# MCU.net
KiCad netlist of a schematic drawn in Altium Designer
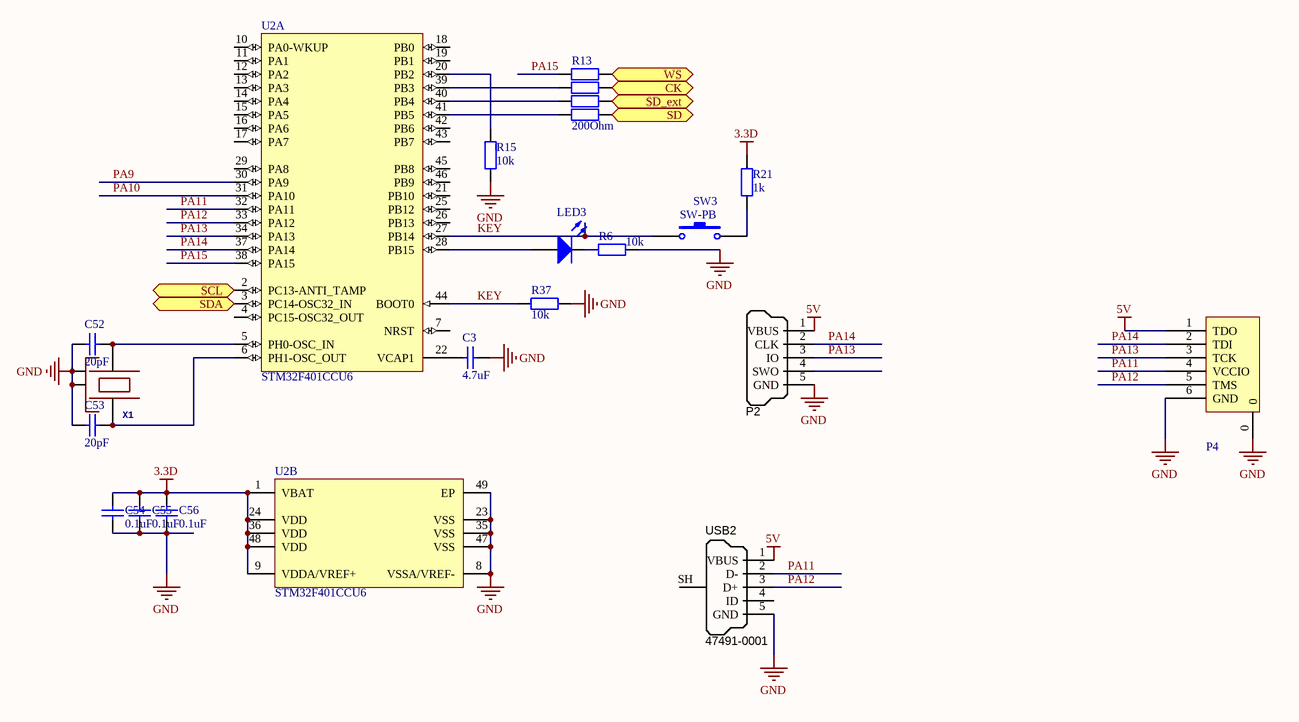
[diagram p0: MCU.SchDoc]

(export (version "E")
  (design (tool "Eeschema 10.0.6"))
  (components
    (comp (ref "C3")
      (value "4.7uF")
      (footprint "0603L")
      (description "Capacitor")
      (fields (field (name "Comment") "Cap") (field (name "PUBLISHER") "Altium Limited"))
      (libsource (lib "RTC6705") (part "Cap"))
    )
    (comp (ref "C52")
      (value "20pF")
      (footprint "0402")
      (description "Capacitor")
      (fields (field (name "Comment") "Cap") (field (name "PUBLISHER") "Altium Limited"))
      (libsource (lib "RTC6705") (part "Cap"))
    )
    (comp (ref "C53")
      (value "20pF")
      (footprint "0402")
      (description "Capacitor")
      (fields (field (name "Comment") "Cap") (field (name "PUBLISHER") "Altium Limited"))
      (libsource (lib "RTC6705") (part "Cap"))
    )
    (comp (ref "C54")
      (value "0.1uF")
      (footprint "0402")
      (description "Capacitor")
      (fields (field (name "Comment") "Cap") (field (name "PUBLISHER") "Altium Limited"))
      (libsource (lib "RTC6705") (part "Cap"))
    )
    (comp (ref "C55")
      (value "0.1uF")
      (footprint "0402")
      (description "Capacitor")
      (fields (field (name "Comment") "Cap") (field (name "PUBLISHER") "Altium Limited"))
      (libsource (lib "RTC6705") (part "Cap"))
    )
    (comp (ref "C56")
      (value "0.1uF")
      (footprint "0402")
      (description "Capacitor")
      (fields (field (name "Comment") "Cap") (field (name "PUBLISHER") "Altium Limited"))
      (libsource (lib "RTC6705") (part "Cap"))
    )
    (comp (ref "LED3")
      (value "LED0")
      (footprint "0603")
      (description "Typical INFRARED GaAs LED")
      (fields (field (name "PUBLISHER") "Altium Limited"))
      (libsource (lib "Miscellaneous Devices") (part "LED0"))
    )
    (comp (ref "P2")
      (value "SWD_MicroUSB")
      (footprint "MICRO-YZX")
      (description "Connector SMD USB Micro Type B middle mount")
      (libsource (lib "sch") (part "SWD_MicroUSB"))
    )
    (comp (ref "P4") (value "JTAG-6P") (footprint "GH1.25-6") (libsource (lib "sch") (part "JTAG-6P")))
    (comp (ref "R6")
      (value "10k")
      (footprint "0402")
      (description "Resistor")
      (fields (field (name "PUBLISHER") "Altium Limited"))
      (libsource (lib "Miscellaneous Devices") (part "Res2"))
    )
    (comp (ref "R13")
      (value "200Ohm")
      (footprint "0402X4")
      (description "Resistor")
      (fields (field (name "Comment") "Res*4") (field (name "PUBLISHER") "Altium Limited"))
      (libsource (lib "sch") (part "Res*4"))
    )
    (comp (ref "R15")
      (value "10k")
      (footprint "0402")
      (description "Resistor")
      (fields (field (name "PUBLISHER") "Altium Limited"))
      (libsource (lib "") (part "Res2_1"))
    )
    (comp (ref "R21")
      (value "1k")
      (footprint "0402")
      (description "Resistor")
      (fields (field (name "PUBLISHER") "Altium Limited"))
      (libsource (lib "") (part "Res2_2"))
    )
    (comp (ref "R37")
      (value "10k")
      (footprint "0402")
      (description "Resistor")
      (fields (field (name "Comment") "Res2") (field (name "PUBLISHER") "Altium Limited"))
      (libsource (lib "RTC6705") (part "Res2"))
    )
    (comp (ref "SW3")
      (value "SW-PB")
      (footprint "SW3x4")
      (description "Switch")
      (fields (field (name "PUBLISHER") "Altium Limited"))
      (libsource (lib "Miscellaneous Devices") (part "SW-PB"))
    )
    (comp (ref "U2")
      (value "STM32F401CCU6")
      (footprint "STM-UFQFPN48_N")
      (fields (field (name "MANUFACTURER") "STMicroelectronics"))
      (libsource (lib "STMicroelectronics STM32 F4") (part "STM32F401CCU6"))
    )
    (comp (ref "USB2")
      (value "USB Micro Type B")
      (footprint "MICRO-YZX")
      (description "Connector SMD USB Micro Type B middle mount")
      (fields (field (name "MANUFACTURER PART NUMBER 1") "47491-0001"))
      (libsource (lib "PBL - Connectors") (part "USB_Micro_TypeB"))
    )
    (comp (ref "X1")
      (value "24.000 KHz 3.2x2.5mm 8-10pf")
      (footprint "OSCILLATOR-2.5x2.0")
      (description "Crystal Oscillator in 3.2x2.5 SMD")
      (libsource (lib "pixhawk2") (part "OSCILLATOR-3.2X2.5"))
    )
  )
  (nets
    (net (code "1") (name "/CK") (class "Default")
      (node (ref "R13") (pin "2") (pinfunction "2_2") (pintype "passive"))
    )
    (net (code "2") (name "/KEY") (class "Default")
      (node (ref "R37") (pin "1") (pinfunction "1_1") (pintype "passive"))
      (node (ref "SW3") (pin "1") (pinfunction "1_1") (pintype "passive"))
      (node (ref "U2") (pin "27") (pinfunction "PB14_27") (pintype "bidirectional"))
      (node (ref "U2") (pin "44") (pinfunction "BOOT0_44") (pintype "input"))
    )
    (net (code "3") (name "/PA9") (class "Default")
      (node (ref "U2") (pin "30") (pinfunction "PA9_30") (pintype "bidirectional"))
    )
    (net (code "4") (name "/PA10") (class "Default")
      (node (ref "U2") (pin "31") (pinfunction "PA10_31") (pintype "bidirectional"))
    )
    (net (code "5") (name "/PA11") (class "Default")
      (node (ref "P4") (pin "4") (pinfunction "VCCIO_4") (pintype "passive"))
      (node (ref "U2") (pin "32") (pinfunction "PA11_32") (pintype "bidirectional"))
      (node (ref "USB2") (pin "2") (pinfunction "D-_2") (pintype "passive"))
    )
    (net (code "6") (name "/PA12") (class "Default")
      (node (ref "P4") (pin "5") (pinfunction "TMS_5") (pintype "passive"))
      (node (ref "U2") (pin "33") (pinfunction "PA12_33") (pintype "bidirectional"))
      (node (ref "USB2") (pin "3") (pinfunction "D+_3") (pintype "passive"))
    )
    (net (code "7") (name "/PA13") (class "Default")
      (node (ref "P2") (pin "3") (pinfunction "IO_3") (pintype "passive"))
      (node (ref "P4") (pin "3") (pinfunction "TCK_3") (pintype "passive"))
      (node (ref "U2") (pin "34") (pinfunction "PA13_34") (pintype "bidirectional"))
    )
    (net (code "8") (name "/PA14") (class "Default")
      (node (ref "P2") (pin "2") (pinfunction "CLK_2") (pintype "passive"))
      (node (ref "P4") (pin "2") (pinfunction "TDI_2") (pintype "passive"))
      (node (ref "U2") (pin "37") (pinfunction "PA14_37") (pintype "bidirectional"))
    )
    (net (code "9") (name "/PA15") (class "Default")
      (node (ref "R13") (pin "8") (pinfunction "8_8") (pintype "passive"))
      (node (ref "U2") (pin "38") (pinfunction "PA15_38") (pintype "bidirectional"))
    )
    (net (code "10") (name "/SCL") (class "Default")
      (node (ref "U2") (pin "2") (pinfunction "PC13-ANTI_TAMP_2") (pintype "bidirectional"))
    )
    (net (code "11") (name "/SD") (class "Default")
      (node (ref "R13") (pin "4") (pinfunction "4_4") (pintype "passive"))
    )
    (net (code "12") (name "/SDA") (class "Default")
      (node (ref "U2") (pin "3") (pinfunction "PC14-OSC32_IN_3") (pintype "bidirectional"))
    )
    (net (code "13") (name "/SD_ext") (class "Default")
      (node (ref "R13") (pin "3") (pinfunction "3_3") (pintype "passive"))
    )
    (net (code "14") (name "/WS") (class "Default")
      (node (ref "R13") (pin "1") (pinfunction "1_1") (pintype "passive"))
    )
    (net (code "15") (name "3.3D") (class "Default")
      (node (ref "C54") (pin "2") (pinfunction "2_2") (pintype "passive"))
      (node (ref "C55") (pin "2") (pinfunction "2_2") (pintype "passive"))
      (node (ref "C56") (pin "2") (pinfunction "2_2") (pintype "passive"))
      (node (ref "R21") (pin "2") (pinfunction "2_2") (pintype "passive"))
      (node (ref "U2") (pin "1") (pinfunction "VBAT_1") (pintype "power_in"))
      (node (ref "U2") (pin "24") (pinfunction "VDD_24") (pintype "power_in"))
      (node (ref "U2") (pin "36") (pinfunction "VDD_36") (pintype "power_in"))
      (node (ref "U2") (pin "48") (pinfunction "VDD_48") (pintype "power_in"))
      (node (ref "U2") (pin "9") (pinfunction "VDDA/VREF+_9") (pintype "power_in"))
    )
    (net (code "16") (name "5V") (class "Default")
      (node (ref "P2") (pin "1") (pinfunction "VBUS_1") (pintype "passive"))
      (node (ref "P4") (pin "1") (pinfunction "TDO_1") (pintype "passive"))
      (node (ref "USB2") (pin "1") (pinfunction "VBUS_1") (pintype "passive"))
    )
    (net (code "17") (name "GND") (class "Default")
      (node (ref "C3") (pin "1") (pinfunction "1_1") (pintype "passive"))
      (node (ref "C52") (pin "1") (pinfunction "1_1") (pintype "passive"))
      (node (ref "C53") (pin "1") (pinfunction "1_1") (pintype "passive"))
      (node (ref "C54") (pin "1") (pinfunction "1_1") (pintype "passive"))
      (node (ref "C55") (pin "1") (pinfunction "1_1") (pintype "passive"))
      (node (ref "C56") (pin "1") (pinfunction "1_1") (pintype "passive"))
      (node (ref "P2") (pin "5") (pinfunction "GND_5") (pintype "passive"))
      (node (ref "P4") (pin "0") (pinfunction "0_0") (pintype "passive"))
      (node (ref "P4") (pin "6") (pinfunction "GND_6") (pintype "passive"))
      (node (ref "R15") (pin "2") (pinfunction "2_2") (pintype "passive"))
      (node (ref "R37") (pin "2") (pinfunction "2_2") (pintype "passive"))
      (node (ref "R6") (pin "2") (pinfunction "2_2") (pintype "passive"))
      (node (ref "U2") (pin "23") (pinfunction "VSS_23") (pintype "power_in"))
      (node (ref "U2") (pin "35") (pinfunction "VSS_35") (pintype "power_in"))
      (node (ref "U2") (pin "47") (pinfunction "VSS_47") (pintype "power_in"))
      (node (ref "U2") (pin "49") (pinfunction "EP_49") (pintype "power_in"))
      (node (ref "U2") (pin "8") (pinfunction "VSSA/VREF-_8") (pintype "power_in"))
      (node (ref "USB2") (pin "5") (pinfunction "GND_5") (pintype "passive"))
      (node (ref "X1") (pin "2") (pinfunction "NC_2_2") (pintype "open_emitter"))
      (node (ref "X1") (pin "4") (pinfunction "NC_4_4") (pintype "open_emitter"))
    )
    (net (code "18") (name "Net-(LED3-A)") (class "Default")
      (node (ref "LED3") (pin "1") (pinfunction "A_1") (pintype "passive"))
      (node (ref "U2") (pin "28") (pinfunction "PB15_28") (pintype "bidirectional"))
    )
    (net (code "19") (name "Net-(LED3-K)") (class "Default")
      (node (ref "LED3") (pin "2") (pinfunction "K_2") (pintype "passive"))
      (node (ref "R6") (pin "1") (pinfunction "1_1") (pintype "passive"))
    )
    (net (code "20") (name "Net-(R21-Pad1)") (class "Default")
      (node (ref "R21") (pin "1") (pinfunction "1_1") (pintype "passive"))
      (node (ref "SW3") (pin "2") (pinfunction "2_2") (pintype "passive"))
    )
    (net (code "21") (name "Net-(U2A-PB2)") (class "Default")
      (node (ref "R15") (pin "1") (pinfunction "1_1") (pintype "passive"))
      (node (ref "U2") (pin "20") (pinfunction "PB2_20") (pintype "bidirectional"))
    )
    (net (code "22") (name "Net-(U2A-PB3)") (class "Default")
      (node (ref "R13") (pin "7") (pinfunction "7_7") (pintype "passive"))
      (node (ref "U2") (pin "39") (pinfunction "PB3_39") (pintype "bidirectional"))
    )
    (net (code "23") (name "Net-(U2A-PB4)") (class "Default")
      (node (ref "R13") (pin "6") (pinfunction "6_6") (pintype "passive"))
      (node (ref "U2") (pin "40") (pinfunction "PB4_40") (pintype "bidirectional"))
    )
    (net (code "24") (name "Net-(U2A-PB5)") (class "Default")
      (node (ref "R13") (pin "5") (pinfunction "5_5") (pintype "passive"))
      (node (ref "U2") (pin "41") (pinfunction "PB5_41") (pintype "bidirectional"))
    )
    (net (code "25") (name "Net-(U2A-PH0-OSC_IN)") (class "Default")
      (node (ref "C52") (pin "2") (pinfunction "2_2") (pintype "passive"))
      (node (ref "U2") (pin "5") (pinfunction "PH0-OSC_IN_5") (pintype "bidirectional"))
      (node (ref "X1") (pin "1") (pinfunction "1_1") (pintype "passive"))
    )
    (net (code "26") (name "Net-(U2A-PH1-OSC_OUT)") (class "Default")
      (node (ref "C53") (pin "2") (pinfunction "2_2") (pintype "passive"))
      (node (ref "U2") (pin "6") (pinfunction "PH1-OSC_OUT_6") (pintype "bidirectional"))
      (node (ref "X1") (pin "3") (pinfunction "3_3") (pintype "passive"))
    )
    (net (code "27") (name "Net-(U2A-VCAP1)") (class "Default")
      (node (ref "C3") (pin "2") (pinfunction "2_2") (pintype "passive"))
      (node (ref "U2") (pin "22") (pinfunction "VCAP1_22") (pintype "power_in"))
    )
    (net (code "28") (name "unconnected-(P2-SWO-Pad4)") (class "Default")
      (node (ref "P2") (pin "4") (pinfunction "SWO_4") (pintype "passive"))
    )
    (net (code "29") (name "unconnected-(U2A-NRST-Pad7)") (class "Default")
      (node (ref "U2") (pin "7") (pinfunction "NRST_7") (pintype "bidirectional"))
    )
    (net (code "30") (name "unconnected-(U2A-PA0-WKUP-Pad10)") (class "Default")
      (node (ref "U2") (pin "10") (pinfunction "PA0-WKUP_10") (pintype "bidirectional"))
    )
    (net (code "31") (name "unconnected-(U2A-PA1-Pad11)") (class "Default")
      (node (ref "U2") (pin "11") (pinfunction "PA1_11") (pintype "bidirectional"))
    )
    (net (code "32") (name "unconnected-(U2A-PA2-Pad12)") (class "Default")
      (node (ref "U2") (pin "12") (pinfunction "PA2_12") (pintype "bidirectional"))
    )
    (net (code "33") (name "unconnected-(U2A-PA3-Pad13)") (class "Default")
      (node (ref "U2") (pin "13") (pinfunction "PA3_13") (pintype "bidirectional"))
    )
    (net (code "34") (name "unconnected-(U2A-PA4-Pad14)") (class "Default")
      (node (ref "U2") (pin "14") (pinfunction "PA4_14") (pintype "bidirectional"))
    )
    (net (code "35") (name "unconnected-(U2A-PA5-Pad15)") (class "Default")
      (node (ref "U2") (pin "15") (pinfunction "PA5_15") (pintype "bidirectional"))
    )
    (net (code "36") (name "unconnected-(U2A-PA6-Pad16)") (class "Default")
      (node (ref "U2") (pin "16") (pinfunction "PA6_16") (pintype "bidirectional"))
    )
    (net (code "37") (name "unconnected-(U2A-PA7-Pad17)") (class "Default")
      (node (ref "U2") (pin "17") (pinfunction "PA7_17") (pintype "bidirectional"))
    )
    (net (code "38") (name "unconnected-(U2A-PA8-Pad29)") (class "Default")
      (node (ref "U2") (pin "29") (pinfunction "PA8_29") (pintype "bidirectional"))
    )
    (net (code "39") (name "unconnected-(U2A-PB0-Pad18)") (class "Default")
      (node (ref "U2") (pin "18") (pinfunction "PB0_18") (pintype "bidirectional"))
    )
    (net (code "40") (name "unconnected-(U2A-PB1-Pad19)") (class "Default")
      (node (ref "U2") (pin "19") (pinfunction "PB1_19") (pintype "bidirectional"))
    )
    (net (code "41") (name "unconnected-(U2A-PB6-Pad42)") (class "Default")
      (node (ref "U2") (pin "42") (pinfunction "PB6_42") (pintype "bidirectional"))
    )
    (net (code "42") (name "unconnected-(U2A-PB7-Pad43)") (class "Default")
      (node (ref "U2") (pin "43") (pinfunction "PB7_43") (pintype "bidirectional"))
    )
    (net (code "43") (name "unconnected-(U2A-PB8-Pad45)") (class "Default")
      (node (ref "U2") (pin "45") (pinfunction "PB8_45") (pintype "bidirectional"))
    )
    (net (code "44") (name "unconnected-(U2A-PB9-Pad46)") (class "Default")
      (node (ref "U2") (pin "46") (pinfunction "PB9_46") (pintype "bidirectional"))
    )
    (net (code "45") (name "unconnected-(U2A-PB10-Pad21)") (class "Default")
      (node (ref "U2") (pin "21") (pinfunction "PB10_21") (pintype "bidirectional"))
    )
    (net (code "46") (name "unconnected-(U2A-PB12-Pad25)") (class "Default")
      (node (ref "U2") (pin "25") (pinfunction "PB12_25") (pintype "bidirectional"))
    )
    (net (code "47") (name "unconnected-(U2A-PB13-Pad26)") (class "Default")
      (node (ref "U2") (pin "26") (pinfunction "PB13_26") (pintype "bidirectional"))
    )
    (net (code "48") (name "unconnected-(U2A-PC15-OSC32_OUT-Pad4)") (class "Default")
      (node (ref "U2") (pin "4") (pinfunction "PC15-OSC32_OUT_4") (pintype "bidirectional"))
    )
    (net (code "49") (name "unconnected-(USB2-ID-Pad4)") (class "Default")
      (node (ref "USB2") (pin "4") (pinfunction "ID_4") (pintype "passive"))
    )
    (net (code "50") (name "unconnected-(USB2-Shell-PadSH)") (class "Default")
      (node (ref "USB2") (pin "SH") (pinfunction "Shell_SH") (pintype "passive"))
    )
  )
)
